# sensor_board_rev2.net
KiCad netlist of a schematic drawn in EAGLE
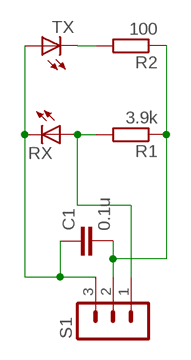
[diagram p0: schematic, sheet 1]

(export (version "E")
  (design (tool "Eeschema 10.0.6"))
  (components
    (comp (ref "C1")
      (value "0.1u")
      (footprint "eagle-import:C025-025X050")
      (libsource (lib "eagle-import") (part "C-EU025-025X050"))
    )
    (comp (ref "R1")
      (value "3.9k")
      (footprint "eagle-import:0207_10")
      (libsource (lib "eagle-import") (part "R-EU_0207/10"))
    )
    (comp (ref "R2")
      (value "100")
      (footprint "eagle-import:0207_10")
      (libsource (lib "eagle-import") (part "R-EU_0207/10"))
    )
    (comp (ref "RX")
      (value "LED5MM")
      (footprint "eagle-import:LED5MM")
      (libsource (lib "eagle-import") (part "LED5MM"))
    )
    (comp (ref "S1")
      (value "MA03-1")
      (footprint "eagle-import:MA03-1")
      (libsource (lib "eagle-import") (part "MA03-1"))
    )
    (comp (ref "TX")
      (value "LED5MM")
      (footprint "eagle-import:LED5MM")
      (libsource (lib "eagle-import") (part "LED5MM"))
    )
  )
  (nets
    (net (code "1") (name "Net-(C1-Pad2)") (class "Default")
      (node (ref "C1") (pin "2") (pinfunction "2_2") (pintype "passive"))
      (node (ref "R1") (pin "1") (pinfunction "1_1") (pintype "passive"))
      (node (ref "R2") (pin "1") (pinfunction "1_1") (pintype "passive"))
      (node (ref "S1") (pin "2") (pinfunction "2_2") (pintype "passive"))
    )
    (net (code "2") (name "Net-(R1-Pad2)") (class "Default")
      (node (ref "R1") (pin "2") (pinfunction "2_2") (pintype "passive"))
      (node (ref "RX") (pin "A") (pinfunction "A_A") (pintype "passive"))
      (node (ref "S1") (pin "1") (pinfunction "1_1") (pintype "passive"))
    )
    (net (code "3") (name "Net-(RX-C)") (class "Default")
      (node (ref "C1") (pin "1") (pinfunction "1_1") (pintype "passive"))
      (node (ref "RX") (pin "K") (pinfunction "C_K") (pintype "passive"))
      (node (ref "S1") (pin "3") (pinfunction "3_3") (pintype "passive"))
      (node (ref "TX") (pin "A") (pinfunction "A_A") (pintype "passive"))
    )
    (net (code "4") (name "Net-(TX-C)") (class "Default")
      (node (ref "R2") (pin "2") (pinfunction "2_2") (pintype "passive"))
      (node (ref "TX") (pin "K") (pinfunction "C_K") (pintype "passive"))
    )
  )
)
